# Nano_attiny85.net
KiCad netlist of a schematic drawn in EAGLE
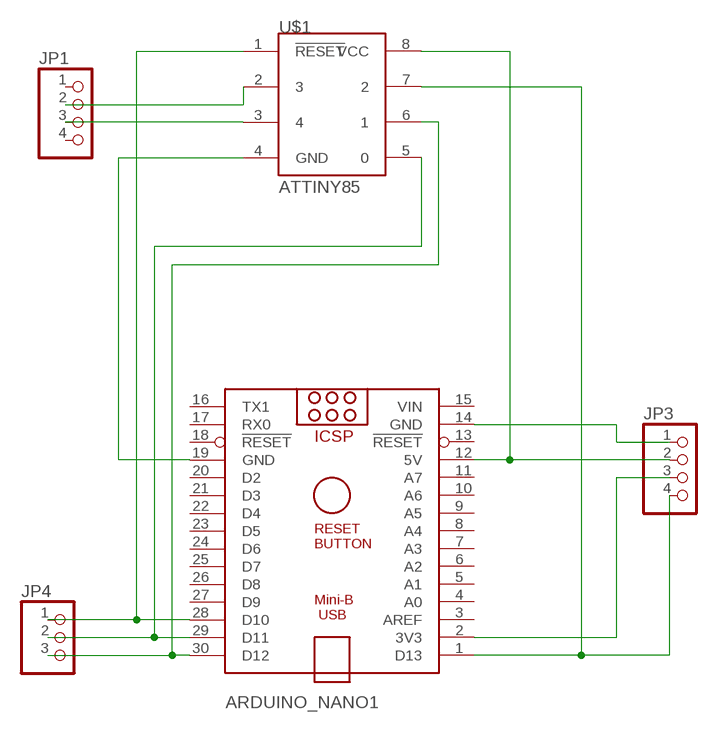
[diagram p0: schematic, sheet 1]

(export (version "E")
  (design (tool "Eeschema 10.0.6"))
  (components
    (comp (ref "ARDUINO_NANO1")
      (value "ARDUINO_NANO")
      (footprint "eagle-import:ARDUINO_NANO")
      (libsource (lib "eagle-import") (part "ARDUINO_NANO"))
    )
    (comp (ref "JP1")
      (value "PINHD-1X4")
      (footprint "eagle-import:1X04")
      (libsource (lib "eagle-import") (part "PINHD-1X4"))
    )
    (comp (ref "JP3")
      (value "PINHD-1X4")
      (footprint "eagle-import:1X04")
      (libsource (lib "eagle-import") (part "PINHD-1X4"))
    )
    (comp (ref "JP4")
      (value "PINHD-1X3")
      (footprint "eagle-import:1X03")
      (libsource (lib "eagle-import") (part "PINHD-1X3"))
    )
    (comp (ref "U$1")
      (value "ATTINY85")
      (footprint "eagle-import:8P3")
      (libsource (lib "eagle-import") (part "ATTINY85"))
    )
  )
  (nets
    (net (code "1") (name "/VIN") (class "Default")
      (node (ref "ARDUINO_NANO1") (pin "15") (pinfunction "VIN_15") (pintype "power_in"))
    )
    (net (code "2") (name "Net-(ARDUINO_NANO1-3V3)") (class "Default")
      (node (ref "ARDUINO_NANO1") (pin "2") (pinfunction "3V3_2") (pintype "output"))
      (node (ref "JP3") (pin "3") (pinfunction "3_3") (pintype "passive"))
    )
    (net (code "3") (name "Net-(ARDUINO_NANO1-5V)") (class "Default")
      (node (ref "ARDUINO_NANO1") (pin "12") (pinfunction "5V_12") (pintype "power_in"))
      (node (ref "JP3") (pin "2") (pinfunction "2_2") (pintype "passive"))
      (node (ref "U$1") (pin "8") (pinfunction "VCC_8") (pintype "power_in"))
    )
    (net (code "4") (name "Net-(ARDUINO_NANO1-D10)") (class "Default")
      (node (ref "ARDUINO_NANO1") (pin "28") (pinfunction "D10_28") (pintype "bidirectional"))
      (node (ref "JP4") (pin "1") (pinfunction "1_1") (pintype "passive"))
      (node (ref "U$1") (pin "1") (pinfunction "~{RESET}_1") (pintype "bidirectional"))
    )
    (net (code "5") (name "Net-(ARDUINO_NANO1-D11)") (class "Default")
      (node (ref "ARDUINO_NANO1") (pin "29") (pinfunction "D11_29") (pintype "bidirectional"))
      (node (ref "JP4") (pin "2") (pinfunction "2_2") (pintype "passive"))
      (node (ref "U$1") (pin "5") (pinfunction "0_5") (pintype "bidirectional"))
    )
    (net (code "6") (name "Net-(ARDUINO_NANO1-D12)") (class "Default")
      (node (ref "ARDUINO_NANO1") (pin "30") (pinfunction "D12_30") (pintype "bidirectional"))
      (node (ref "JP4") (pin "3") (pinfunction "3_3") (pintype "passive"))
      (node (ref "U$1") (pin "6") (pinfunction "1_6") (pintype "bidirectional"))
    )
    (net (code "7") (name "Net-(ARDUINO_NANO1-D13)") (class "Default")
      (node (ref "ARDUINO_NANO1") (pin "1") (pinfunction "D13_1") (pintype "bidirectional"))
      (node (ref "JP3") (pin "4") (pinfunction "4_4") (pintype "passive"))
      (node (ref "U$1") (pin "7") (pinfunction "2_7") (pintype "bidirectional"))
    )
    (net (code "8") (name "Net-(ARDUINO_NANO1-GND-Pad14)") (class "Default")
      (node (ref "ARDUINO_NANO1") (pin "14") (pinfunction "GND_14") (pintype "power_in"))
      (node (ref "JP3") (pin "1") (pinfunction "1_1") (pintype "passive"))
    )
    (net (code "9") (name "Net-(U$1-3)") (class "Default")
      (node (ref "JP1") (pin "2") (pinfunction "2_2") (pintype "passive"))
      (node (ref "U$1") (pin "2") (pinfunction "3_2") (pintype "bidirectional"))
    )
    (net (code "10") (name "Net-(U$1-4)") (class "Default")
      (node (ref "JP1") (pin "3") (pinfunction "3_3") (pintype "passive"))
      (node (ref "U$1") (pin "3") (pinfunction "4_3") (pintype "bidirectional"))
    )
    (net (code "11") (name "Net-(U$1-GND)") (class "Default")
      (node (ref "ARDUINO_NANO1") (pin "19") (pinfunction "GND_19") (pintype "power_in"))
      (node (ref "U$1") (pin "4") (pinfunction "GND_4") (pintype "power_in"))
    )
    (net (code "12") (name "unconnected-(ARDUINO_NANO1-A0-Pad4)") (class "Default")
      (node (ref "ARDUINO_NANO1") (pin "4") (pinfunction "A0_4") (pintype "bidirectional"))
    )
    (net (code "13") (name "unconnected-(ARDUINO_NANO1-A1-Pad5)") (class "Default")
      (node (ref "ARDUINO_NANO1") (pin "5") (pinfunction "A1_5") (pintype "bidirectional"))
    )
    (net (code "14") (name "unconnected-(ARDUINO_NANO1-A2-Pad6)") (class "Default")
      (node (ref "ARDUINO_NANO1") (pin "6") (pinfunction "A2_6") (pintype "bidirectional"))
    )
    (net (code "15") (name "unconnected-(ARDUINO_NANO1-A3-Pad7)") (class "Default")
      (node (ref "ARDUINO_NANO1") (pin "7") (pinfunction "A3_7") (pintype "bidirectional"))
    )
    (net (code "16") (name "unconnected-(ARDUINO_NANO1-A4-Pad8)") (class "Default")
      (node (ref "ARDUINO_NANO1") (pin "8") (pinfunction "A4_8") (pintype "bidirectional"))
    )
    (net (code "17") (name "unconnected-(ARDUINO_NANO1-A5-Pad9)") (class "Default")
      (node (ref "ARDUINO_NANO1") (pin "9") (pinfunction "A5_9") (pintype "bidirectional"))
    )
    (net (code "18") (name "unconnected-(ARDUINO_NANO1-A6-Pad10)") (class "Default")
      (node (ref "ARDUINO_NANO1") (pin "10") (pinfunction "A6_10") (pintype "bidirectional"))
    )
    (net (code "19") (name "unconnected-(ARDUINO_NANO1-A7-Pad11)") (class "Default")
      (node (ref "ARDUINO_NANO1") (pin "11") (pinfunction "A7_11") (pintype "bidirectional"))
    )
    (net (code "20") (name "unconnected-(ARDUINO_NANO1-AREF-Pad3)") (class "Default")
      (node (ref "ARDUINO_NANO1") (pin "3") (pinfunction "AREF_3") (pintype "input"))
    )
    (net (code "21") (name "unconnected-(ARDUINO_NANO1-D2-Pad20)") (class "Default")
      (node (ref "ARDUINO_NANO1") (pin "20") (pinfunction "D2_20") (pintype "bidirectional"))
    )
    (net (code "22") (name "unconnected-(ARDUINO_NANO1-D3-Pad21)") (class "Default")
      (node (ref "ARDUINO_NANO1") (pin "21") (pinfunction "D3_21") (pintype "bidirectional"))
    )
    (net (code "23") (name "unconnected-(ARDUINO_NANO1-D4-Pad22)") (class "Default")
      (node (ref "ARDUINO_NANO1") (pin "22") (pinfunction "D4_22") (pintype "bidirectional"))
    )
    (net (code "24") (name "unconnected-(ARDUINO_NANO1-D5-Pad23)") (class "Default")
      (node (ref "ARDUINO_NANO1") (pin "23") (pinfunction "D5_23") (pintype "bidirectional"))
    )
    (net (code "25") (name "unconnected-(ARDUINO_NANO1-D6-Pad24)") (class "Default")
      (node (ref "ARDUINO_NANO1") (pin "24") (pinfunction "D6_24") (pintype "bidirectional"))
    )
    (net (code "26") (name "unconnected-(ARDUINO_NANO1-D7-Pad25)") (class "Default")
      (node (ref "ARDUINO_NANO1") (pin "25") (pinfunction "D7_25") (pintype "bidirectional"))
    )
    (net (code "27") (name "unconnected-(ARDUINO_NANO1-D8-Pad26)") (class "Default")
      (node (ref "ARDUINO_NANO1") (pin "26") (pinfunction "D8_26") (pintype "bidirectional"))
    )
    (net (code "28") (name "unconnected-(ARDUINO_NANO1-D9-Pad27)") (class "Default")
      (node (ref "ARDUINO_NANO1") (pin "27") (pinfunction "D9_27") (pintype "bidirectional"))
    )
    (net (code "29") (name "unconnected-(ARDUINO_NANO1-RX0-Pad17)") (class "Default")
      (node (ref "ARDUINO_NANO1") (pin "17") (pinfunction "RX0_17") (pintype "bidirectional"))
    )
    (net (code "30") (name "unconnected-(ARDUINO_NANO1-TX1-Pad16)") (class "Default")
      (node (ref "ARDUINO_NANO1") (pin "16") (pinfunction "TX1_16") (pintype "bidirectional"))
    )
    (net (code "31") (name "unconnected-(ARDUINO_NANO1-~{RESET}-Pad13)") (class "Default")
      (node (ref "ARDUINO_NANO1") (pin "13") (pinfunction "~{RESET}_13") (pintype "input"))
    )
    (net (code "32") (name "unconnected-(ARDUINO_NANO1-~{RESET}-Pad18)") (class "Default")
      (node (ref "ARDUINO_NANO1") (pin "18") (pinfunction "~{RESET}_18") (pintype "input"))
    )
    (net (code "33") (name "unconnected-(JP1-Pad1)") (class "Default")
      (node (ref "JP1") (pin "1") (pinfunction "1_1") (pintype "passive"))
    )
    (net (code "34") (name "unconnected-(JP1-Pad4)") (class "Default")
      (node (ref "JP1") (pin "4") (pinfunction "4_4") (pintype "passive"))
    )
  )
)
